# CAN.net
KiCad netlist of a schematic drawn in Altium Designer
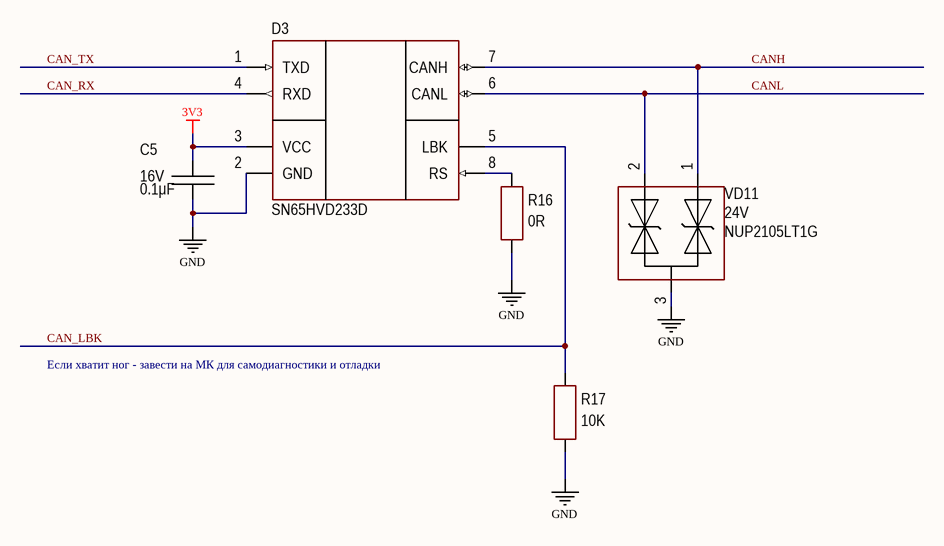
[diagram p0: CAN.SchDoc]

(export (version "E")
  (design (tool "Eeschema 10.0.6"))
  (components
    (comp (ref "C5")
      (value "0.1μF")
      (footprint "CAP: 0805")
      (fields
        (field (name "MANUFACTURER") "Yageo")
        (field (name "PARTNUMBER") "CC0805KRX7R7BB104")
        (field (name "VALUEMANUFACTURERPARTNUMBER") "Ceramic capacitor, 0.1μF, X7R, ±10%, 16V, 0805, -55...+125°C")
        (field (name "VOLTAGE") "16V")
      )
      (libsource (lib "capacitor") (part "Ceramic_0805"))
    )
    (comp (ref "D3")
      (value "~")
      (footprint "8-SOIC")
      (description "CAN")
      (fields
        (field (name "MANUFACTURER") "Texas Instruments")
        (field (name "VALUEMANUFACTURERPARTNUMBER") "IC CAN transceiver, 1Mbps, Half-duplex, 3...3.6V, -40...+85°C, 8-SOIC")
        (field (name "PARTNUMBER") "SN65HVD233D")
      )
      (libsource (lib "ic-interface") (part "SN65HVD231DR"))
    )
    (comp (ref "R16")
      (value "0R")
      (footprint "RES: 1206")
      (fields
        (field (name "MANUFACTURER") "Yageo")
        (field (name "PARTNUMBER") "RC1206JR-07100RL")
        (field (name "VALUEMANUFACTURERPARTNUMBER") "Resistor film, 0R, ±5%, 1206, 0.25W, -55...+125°C")
      )
      (libsource (lib "resistor") (part "Resistor_1206"))
    )
    (comp (ref "R17")
      (value "10K")
      (footprint "RES: 1206")
      (fields
        (field (name "MANUFACTURER") "Yageo")
        (field (name "PARTNUMBER") "RC1206JR-07100RL")
        (field (name "VALUEMANUFACTURERPARTNUMBER") "Resistor film, 10K, ±5%, 1206, 0.25W, -55...+125°C")
      )
      (libsource (lib "resistor") (part "Resistor_1206"))
    )
    (comp (ref "VD11")
      (value "~")
      (footprint "SOT23")
      (fields
        (field (name "MANUFACTURER") "Diodes Incorporated")
        (field (name "VALUEMANUFACTURERPARTNUMBER") "Zener diode, 24V, 500mW, 0.9V, 17Ohm, SOD-123, -55...+150°C")
        (field (name "VOLTAGE") "24V")
        (field (name "PARTNUMBER") "NUP2105LT1G")
      )
      (libsource (lib "diode") (part "TVS_array"))
    )
  )
  (nets
    (net (code "1") (name "/CANH") (class "Default")
      (node (ref "D3") (pin "7") (pinfunction "CANH_7") (pintype "bidirectional"))
      (node (ref "VD11") (pin "1") (pintype "passive"))
    )
    (net (code "2") (name "/CANL") (class "Default")
      (node (ref "D3") (pin "6") (pinfunction "CANL_6") (pintype "bidirectional"))
      (node (ref "VD11") (pin "2") (pintype "passive"))
    )
    (net (code "3") (name "/CAN_LBK") (class "Default")
      (node (ref "D3") (pin "5") (pinfunction "LBK_5") (pintype "passive"))
      (node (ref "R17") (pin "2") (pinfunction "2_2") (pintype "passive"))
    )
    (net (code "4") (name "/CAN_RX") (class "Default")
      (node (ref "D3") (pin "4") (pinfunction "RXD_4") (pintype "output"))
    )
    (net (code "5") (name "/CAN_TX") (class "Default")
      (node (ref "D3") (pin "1") (pinfunction "TXD_1") (pintype "input"))
    )
    (net (code "6") (name "3V3") (class "Default")
      (node (ref "C5") (pin "2") (pinfunction "2_2") (pintype "passive"))
      (node (ref "D3") (pin "3") (pinfunction "VCC_3") (pintype "passive"))
    )
    (net (code "7") (name "GND") (class "Default")
      (node (ref "C5") (pin "1") (pinfunction "1_1") (pintype "passive"))
      (node (ref "D3") (pin "2") (pinfunction "GND_2") (pintype "passive"))
      (node (ref "R16") (pin "1") (pinfunction "1_1") (pintype "passive"))
      (node (ref "R17") (pin "1") (pinfunction "1_1") (pintype "passive"))
      (node (ref "VD11") (pin "3") (pintype "passive"))
    )
    (net (code "8") (name "Net-(D3-RS)") (class "Default")
      (node (ref "D3") (pin "8") (pinfunction "RS_8") (pintype "input"))
      (node (ref "R16") (pin "2") (pinfunction "2_2") (pintype "passive"))
    )
  )
)
